# Adapter_board.net
KiCad netlist of a schematic drawn in Altium Designer
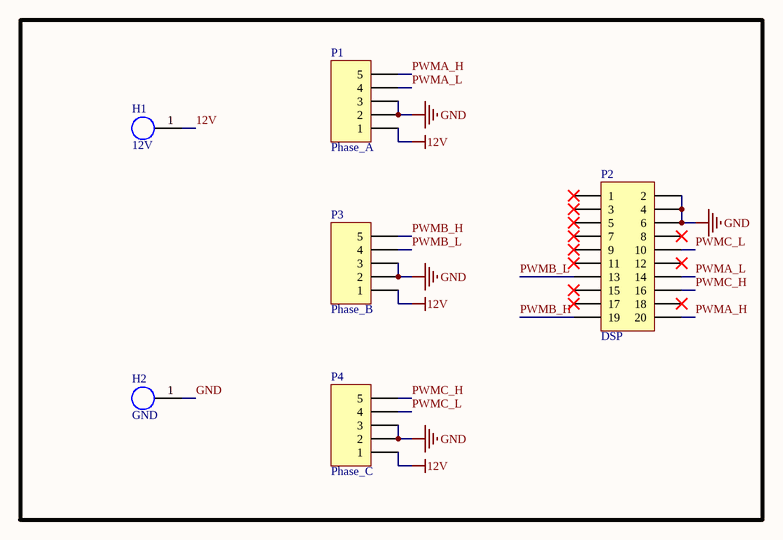
[diagram p0: Adapter_board .SchDoc]

(export (version "E")
  (design (tool "Eeschema 10.0.6"))
  (components
    (comp (ref "H1") (value "12V") (footprint "HOLE") (libsource (lib "Adapter_board") (part "HOLE")))
    (comp (ref "H2") (value "GND") (footprint "HOLE") (libsource (lib "Adapter_board") (part "HOLE")))
    (comp (ref "P1")
      (value "Phase_A")
      (footprint "HDR1X5")
      (description "Header, 5-Pin")
      (fields (field (name "PUBLISHER") "Altium Limited"))
      (libsource (lib "Miscellaneous Connectors") (part "Header 5"))
    )
    (comp (ref "P2")
      (value "DSP")
      (footprint "HDR2X10")
      (description "Header, 10-Pin, Dual row")
      (fields (field (name "PUBLISHER") "Altium Limited"))
      (libsource (lib "Miscellaneous Connectors") (part "Header 10X2"))
    )
    (comp (ref "P3")
      (value "Phase_B")
      (footprint "HDR1X5")
      (description "Header, 5-Pin")
      (fields (field (name "PUBLISHER") "Altium Limited"))
      (libsource (lib "Miscellaneous Connectors") (part "Header 5"))
    )
    (comp (ref "P4")
      (value "Phase_C")
      (footprint "HDR1X5")
      (description "Header, 5-Pin")
      (fields (field (name "PUBLISHER") "Altium Limited"))
      (libsource (lib "Miscellaneous Connectors") (part "Header 5"))
    )
  )
  (nets
    (net (code "1") (name "/PWMA_H") (class "Default")
      (node (ref "P1") (pin "5") (pinfunction "5_5") (pintype "passive"))
      (node (ref "P2") (pin "20") (pinfunction "20_20") (pintype "passive"))
    )
    (net (code "2") (name "/PWMA_L") (class "Default")
      (node (ref "P1") (pin "4") (pinfunction "4_4") (pintype "passive"))
      (node (ref "P2") (pin "14") (pinfunction "14_14") (pintype "passive"))
    )
    (net (code "3") (name "/PWMB_H") (class "Default")
      (node (ref "P2") (pin "19") (pinfunction "19_19") (pintype "passive"))
      (node (ref "P3") (pin "5") (pinfunction "5_5") (pintype "passive"))
    )
    (net (code "4") (name "/PWMB_L") (class "Default")
      (node (ref "P2") (pin "13") (pinfunction "13_13") (pintype "passive"))
      (node (ref "P3") (pin "4") (pinfunction "4_4") (pintype "passive"))
    )
    (net (code "5") (name "/PWMC_H") (class "Default")
      (node (ref "P2") (pin "16") (pinfunction "16_16") (pintype "passive"))
      (node (ref "P4") (pin "5") (pinfunction "5_5") (pintype "passive"))
    )
    (net (code "6") (name "/PWMC_L") (class "Default")
      (node (ref "P2") (pin "10") (pinfunction "10_10") (pintype "passive"))
      (node (ref "P4") (pin "4") (pinfunction "4_4") (pintype "passive"))
    )
    (net (code "7") (name "12V") (class "Default")
      (node (ref "H1") (pin "1") (pintype "passive"))
      (node (ref "P1") (pin "1") (pinfunction "1_1") (pintype "passive"))
      (node (ref "P3") (pin "1") (pinfunction "1_1") (pintype "passive"))
      (node (ref "P4") (pin "1") (pinfunction "1_1") (pintype "passive"))
    )
    (net (code "8") (name "GND") (class "Default")
      (node (ref "H2") (pin "1") (pintype "passive"))
      (node (ref "P1") (pin "2") (pinfunction "2_2") (pintype "passive"))
      (node (ref "P1") (pin "3") (pinfunction "3_3") (pintype "passive"))
      (node (ref "P2") (pin "2") (pinfunction "2_2") (pintype "passive"))
      (node (ref "P2") (pin "4") (pinfunction "4_4") (pintype "passive"))
      (node (ref "P2") (pin "6") (pinfunction "6_6") (pintype "passive"))
      (node (ref "P3") (pin "2") (pinfunction "2_2") (pintype "passive"))
      (node (ref "P3") (pin "3") (pinfunction "3_3") (pintype "passive"))
      (node (ref "P4") (pin "2") (pinfunction "2_2") (pintype "passive"))
      (node (ref "P4") (pin "3") (pinfunction "3_3") (pintype "passive"))
    )
    (net (code "9") (name "unconnected-(P2-Pad1)") (class "Default")
      (node (ref "P2") (pin "1") (pinfunction "1_1") (pintype "passive+no_connect"))
    )
    (net (code "10") (name "unconnected-(P2-Pad3)") (class "Default")
      (node (ref "P2") (pin "3") (pinfunction "3_3") (pintype "passive+no_connect"))
    )
    (net (code "11") (name "unconnected-(P2-Pad5)") (class "Default")
      (node (ref "P2") (pin "5") (pinfunction "5_5") (pintype "passive+no_connect"))
    )
    (net (code "12") (name "unconnected-(P2-Pad7)") (class "Default")
      (node (ref "P2") (pin "7") (pinfunction "7_7") (pintype "passive+no_connect"))
    )
    (net (code "13") (name "unconnected-(P2-Pad8)") (class "Default")
      (node (ref "P2") (pin "8") (pinfunction "8_8") (pintype "passive+no_connect"))
    )
    (net (code "14") (name "unconnected-(P2-Pad9)") (class "Default")
      (node (ref "P2") (pin "9") (pinfunction "9_9") (pintype "passive+no_connect"))
    )
    (net (code "15") (name "unconnected-(P2-Pad11)") (class "Default")
      (node (ref "P2") (pin "11") (pinfunction "11_11") (pintype "passive+no_connect"))
    )
    (net (code "16") (name "unconnected-(P2-Pad12)") (class "Default")
      (node (ref "P2") (pin "12") (pinfunction "12_12") (pintype "passive+no_connect"))
    )
    (net (code "17") (name "unconnected-(P2-Pad15)") (class "Default")
      (node (ref "P2") (pin "15") (pinfunction "15_15") (pintype "passive+no_connect"))
    )
    (net (code "18") (name "unconnected-(P2-Pad17)") (class "Default")
      (node (ref "P2") (pin "17") (pinfunction "17_17") (pintype "passive+no_connect"))
    )
    (net (code "19") (name "unconnected-(P2-Pad18)") (class "Default")
      (node (ref "P2") (pin "18") (pinfunction "18_18") (pintype "passive+no_connect"))
    )
  )
)
